# schematic.net
KiCad netlist of a schematic drawn in EasyEDA
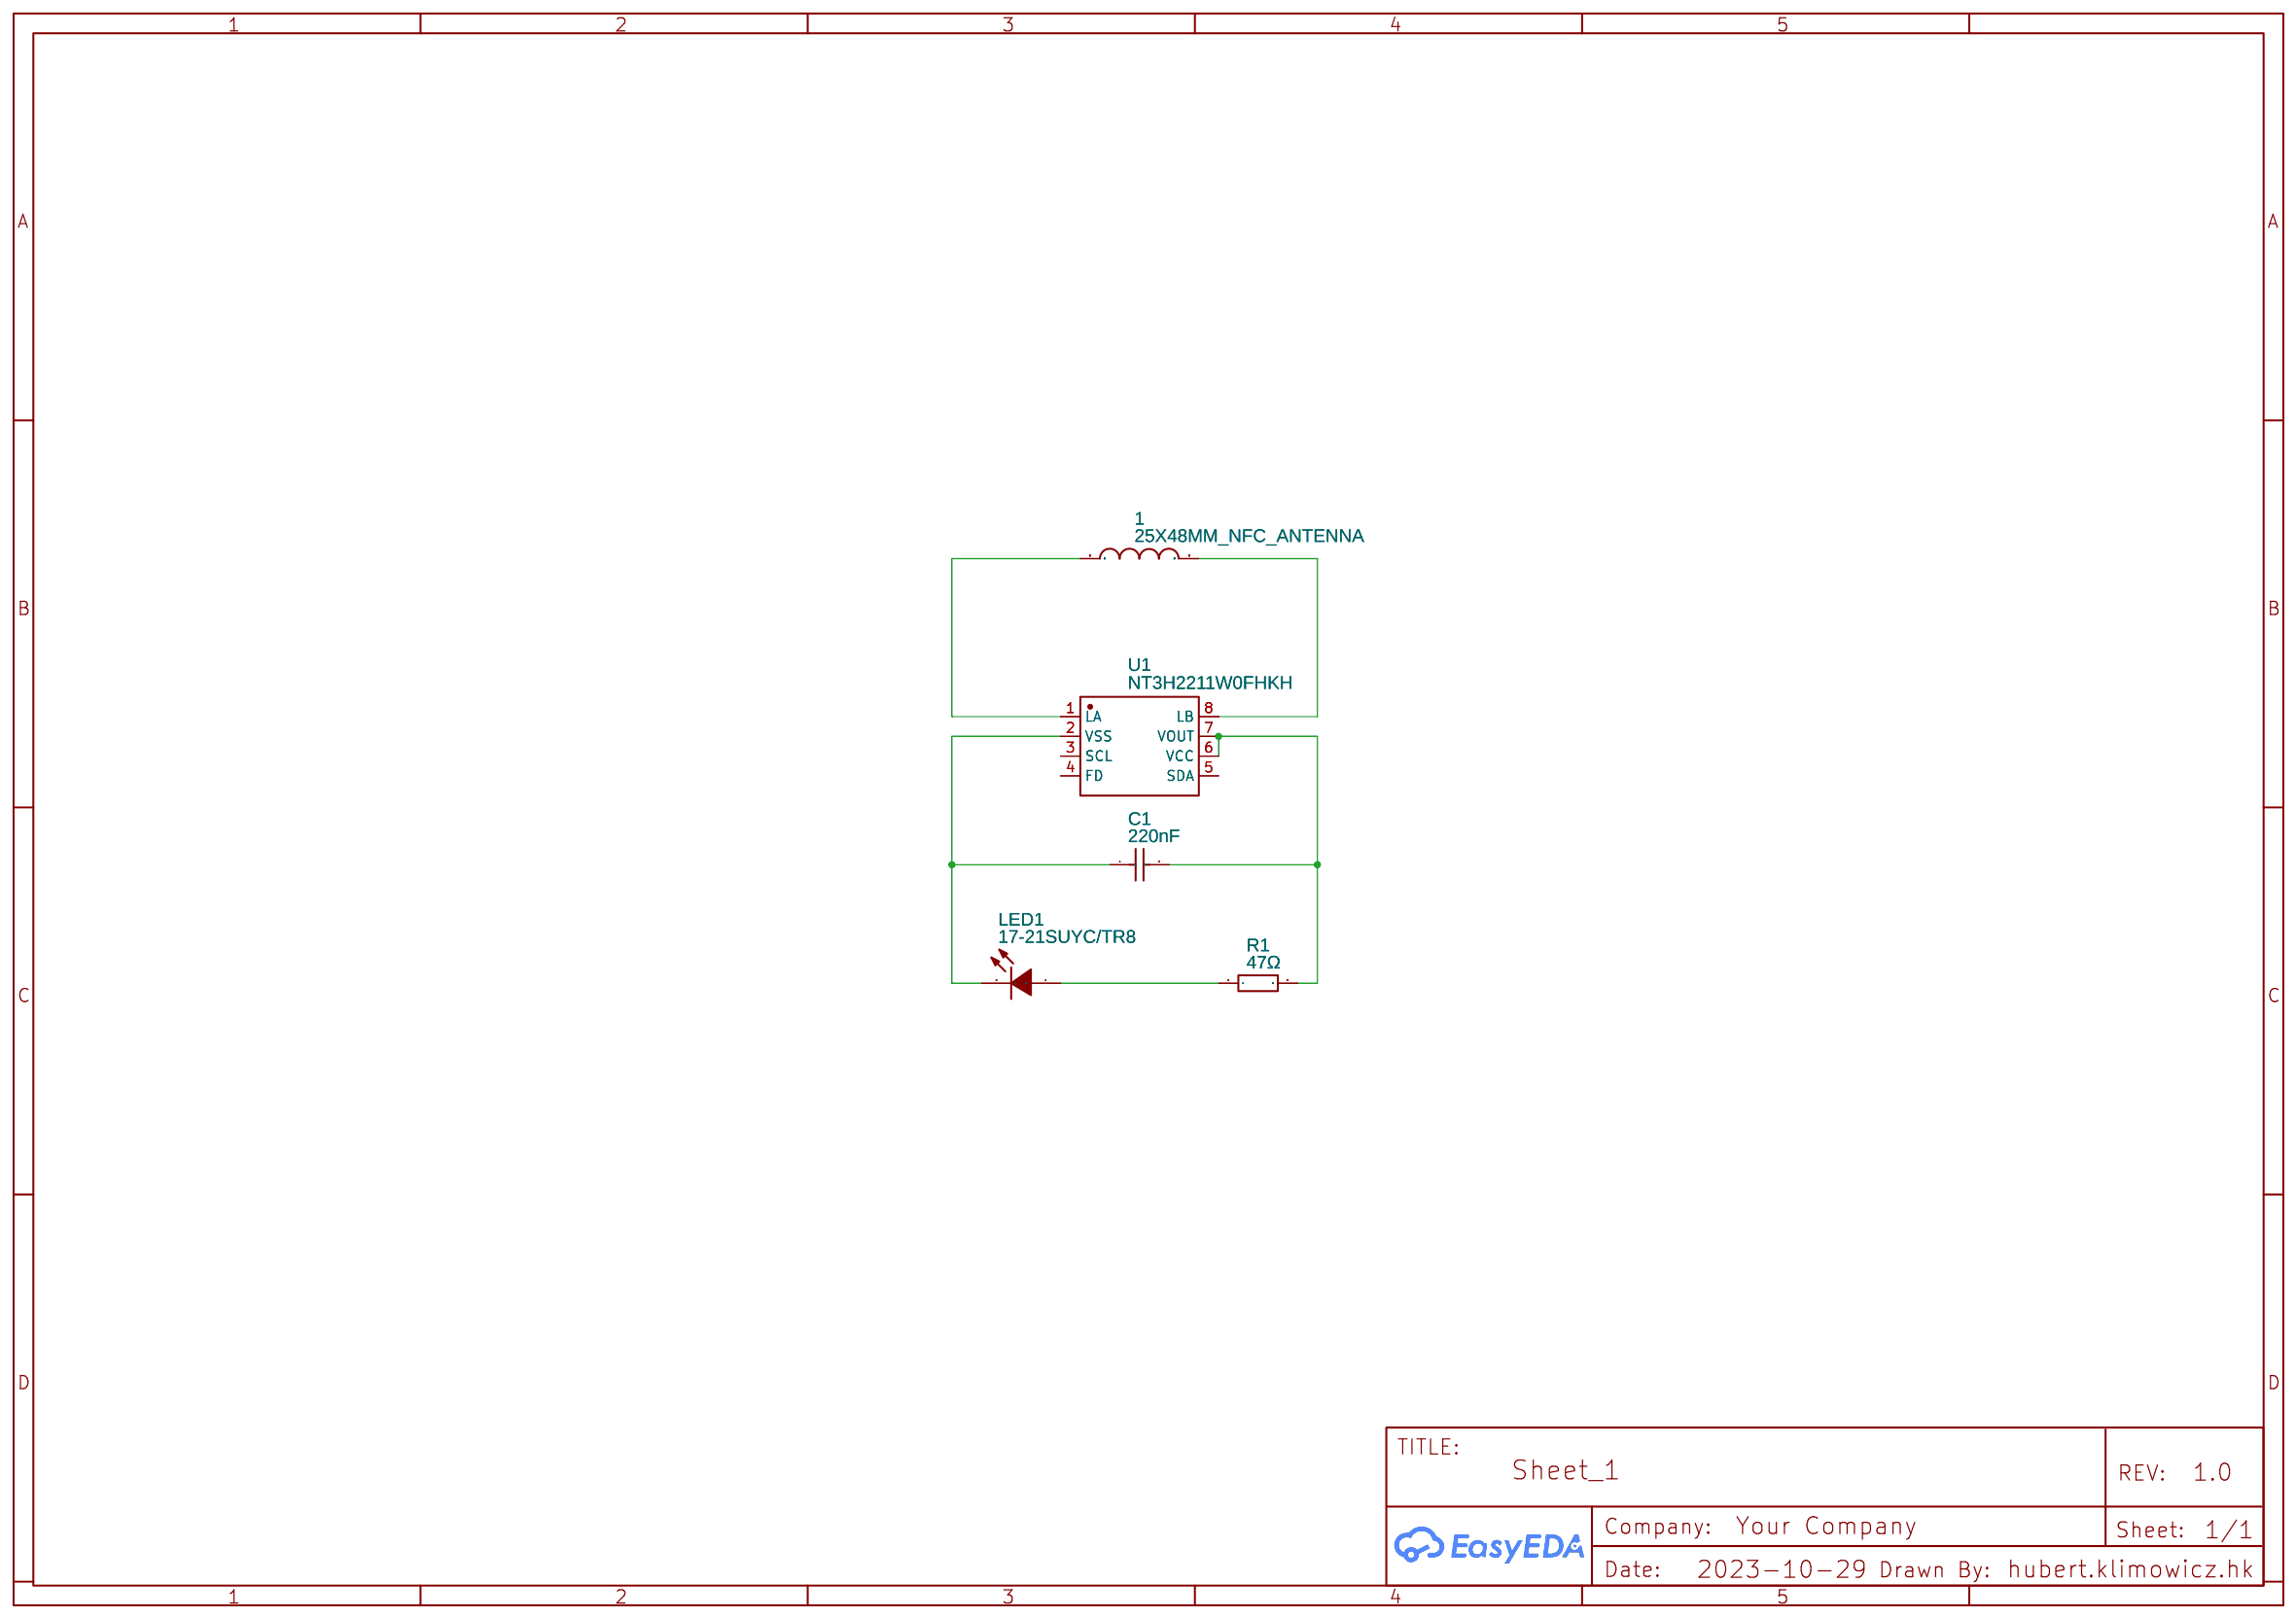
[diagram p0: schematic sheet]

(export (version "E")
  (design (tool "Eeschema 10.0.6"))
  (components
    (comp (ref "1") (value "25X48MM_NFC_ANTENNA") (libsource (lib "") (part "25X48MM_NFC_ANTENNA")))
    (comp (ref "C1")
      (value "220nF")
      (fields
        (field (name "Manufacturer Part") "CL10B224KA8NNNC")
        (field (name "Manufacturer") "SAMSUNG(三星)")
      )
      (libsource (lib "") (part "CL10B224KA8NNNC"))
    )
    (comp (ref "LED1")
      (value "17-21SUYC/TR8")
      (fields (field (name "Manufacturer Part") "KT-0805黄灯") (field (name "Manufacturer") "KENTO"))
      (libsource (lib "") (part "17-21SUYC/TR8"))
    )
    (comp (ref "R1")
      (value "47Ω")
      (fields
        (field (name "Manufacturer Part") "0603WAF470JT5E")
        (field (name "Manufacturer") "UNI-ROYAL(厚声)")
      )
      (libsource (lib "") (part "0603WAF470JT5E"))
    )
    (comp (ref "U1")
      (value "NT3H2211W0FHKH")
      (fields (field (name "Manufacturer") "NXP(恩智浦)"))
      (libsource (lib "") (part "NT3H2211W0FHKH"))
    )
  )
  (nets
    (net (code "1") (name "Net-(LED1-+)") (class "Default")
      (node (ref "LED1") (pin "1") (pinfunction "+_1") (pintype "unspecified"))
      (node (ref "R1") (pin "1") (pinfunction "1_1") (pintype "input"))
    )
    (net (code "2") (name "Net-(LED1--)") (class "Default")
      (node (ref "C1") (pin "1") (pinfunction "1_1") (pintype "input"))
      (node (ref "LED1") (pin "2") (pinfunction "-_2") (pintype "unspecified"))
      (node (ref "U1") (pin "2") (pinfunction "VSS_2") (pintype "unspecified"))
    )
    (net (code "3") (name "Net-(U1-LA)") (class "Default")
      (node (ref "1") (pin "P$1") (pinfunction "P$1_P$1") (pintype "bidirectional"))
      (node (ref "U1") (pin "1") (pinfunction "LA_1") (pintype "unspecified"))
    )
    (net (code "4") (name "Net-(U1-LB)") (class "Default")
      (node (ref "1") (pin "P$2") (pinfunction "P$2_P$2") (pintype "bidirectional"))
      (node (ref "U1") (pin "8") (pinfunction "LB_8") (pintype "unspecified"))
    )
    (net (code "5") (name "Net-(U1-VCC)") (class "Default")
      (node (ref "C1") (pin "2") (pinfunction "2_2") (pintype "input"))
      (node (ref "R1") (pin "2") (pinfunction "2_2") (pintype "input"))
      (node (ref "U1") (pin "6") (pinfunction "VCC_6") (pintype "unspecified"))
      (node (ref "U1") (pin "7") (pinfunction "VOUT_7") (pintype "unspecified"))
    )
    (net (code "6") (name "unconnected-(U1-FD-Pad4)") (class "Default")
      (node (ref "U1") (pin "4") (pinfunction "FD_4") (pintype "unspecified"))
    )
    (net (code "7") (name "unconnected-(U1-SCL-Pad3)") (class "Default")
      (node (ref "U1") (pin "3") (pinfunction "SCL_3") (pintype "unspecified"))
    )
    (net (code "8") (name "unconnected-(U1-SDA-Pad5)") (class "Default")
      (node (ref "U1") (pin "5") (pinfunction "SDA_5") (pintype "unspecified"))
    )
  )
)
